# Extender_Jumper.net
KiCad netlist of a schematic drawn in EAGLE
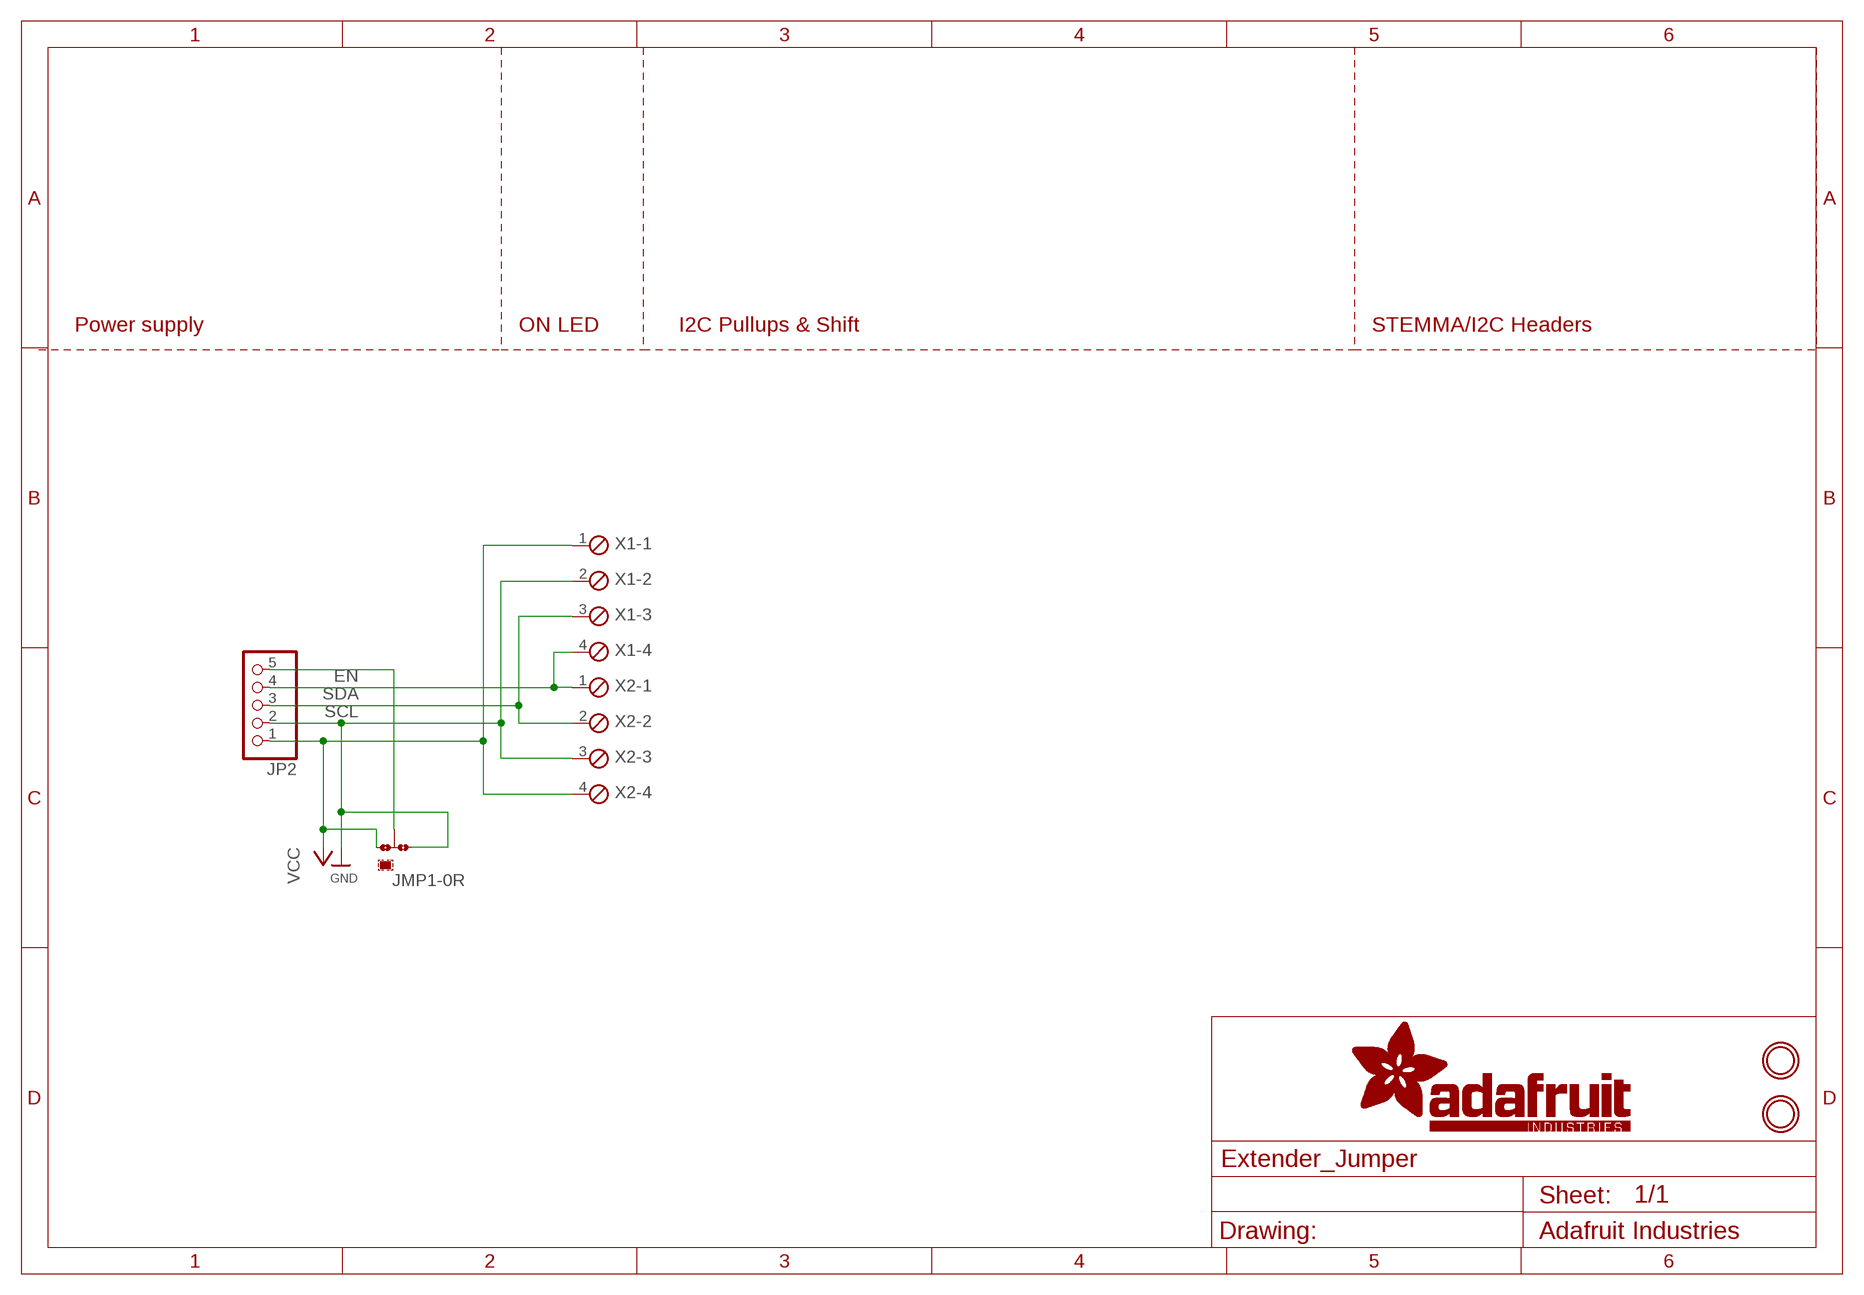
[diagram p0: schematic, sheet 1]

(export (version "E")
  (design (tool "Eeschema 10.0.6"))
  (components
    (comp (ref "JMP1")
      (value "0R-JUMPA")
      (footprint "eagle-import:A0R-JMP")
      (libsource (lib "eagle-import") (part "0R-JUMPA"))
    )
    (comp (ref "JP2")
      (value "HEADER-1X570MIL")
      (footprint "eagle-import:1X05_ROUND_70")
      (libsource (lib "eagle-import") (part "HEADER-1X570MIL"))
    )
    (comp (ref "U$19")
      (value "MOUNTINGHOLE2.5")
      (footprint "eagle-import:MOUNTINGHOLE_2.5_PLATED")
      (libsource (lib "eagle-import") (part "MOUNTINGHOLE2.5"))
    )
    (comp (ref "U$21")
      (value "MOUNTINGHOLE2.5")
      (footprint "eagle-import:MOUNTINGHOLE_2.5_PLATED")
      (libsource (lib "eagle-import") (part "MOUNTINGHOLE2.5"))
    )
    (comp (ref "X1")
      (value "MPT4")
      (footprint "eagle-import:4POL254")
      (libsource (lib "eagle-import") (part "MPT4"))
    )
    (comp (ref "X2")
      (value "MPT4")
      (footprint "eagle-import:4POL254")
      (libsource (lib "eagle-import") (part "MPT4"))
    )
  )
  (nets
    (net (code "1") (name "/EN") (class "Default")
      (node (ref "JMP1") (pin "2") (pinfunction "2_2") (pintype "passive"))
      (node (ref "JP2") (pin "5") (pinfunction "5_5") (pintype "passive"))
    )
    (net (code "2") (name "/SCL") (class "Default")
      (node (ref "JP2") (pin "3") (pinfunction "3_3") (pintype "passive"))
      (node (ref "X1") (pin "3") (pinfunction "1_3") (pintype "passive"))
      (node (ref "X2") (pin "2") (pinfunction "1_2") (pintype "passive"))
    )
    (net (code "3") (name "/SDA") (class "Default")
      (node (ref "JP2") (pin "4") (pinfunction "4_4") (pintype "passive"))
      (node (ref "X1") (pin "4") (pinfunction "1_4") (pintype "passive"))
      (node (ref "X2") (pin "1") (pinfunction "1_1") (pintype "passive"))
    )
    (net (code "4") (name "GND") (class "Default")
      (node (ref "JMP1") (pin "3") (pinfunction "3_3") (pintype "passive"))
      (node (ref "JP2") (pin "2") (pinfunction "2_2") (pintype "passive"))
      (node (ref "X1") (pin "2") (pinfunction "1_2") (pintype "passive"))
      (node (ref "X2") (pin "3") (pinfunction "1_3") (pintype "passive"))
    )
    (net (code "5") (name "VCC") (class "Default")
      (node (ref "JMP1") (pin "1") (pinfunction "1_1") (pintype "passive"))
      (node (ref "JP2") (pin "1") (pinfunction "1_1") (pintype "passive"))
      (node (ref "X1") (pin "1") (pinfunction "1_1") (pintype "passive"))
      (node (ref "X2") (pin "4") (pinfunction "1_4") (pintype "passive"))
    )
  )
)
